# EnvSens.net
KiCad netlist of a schematic drawn in EAGLE
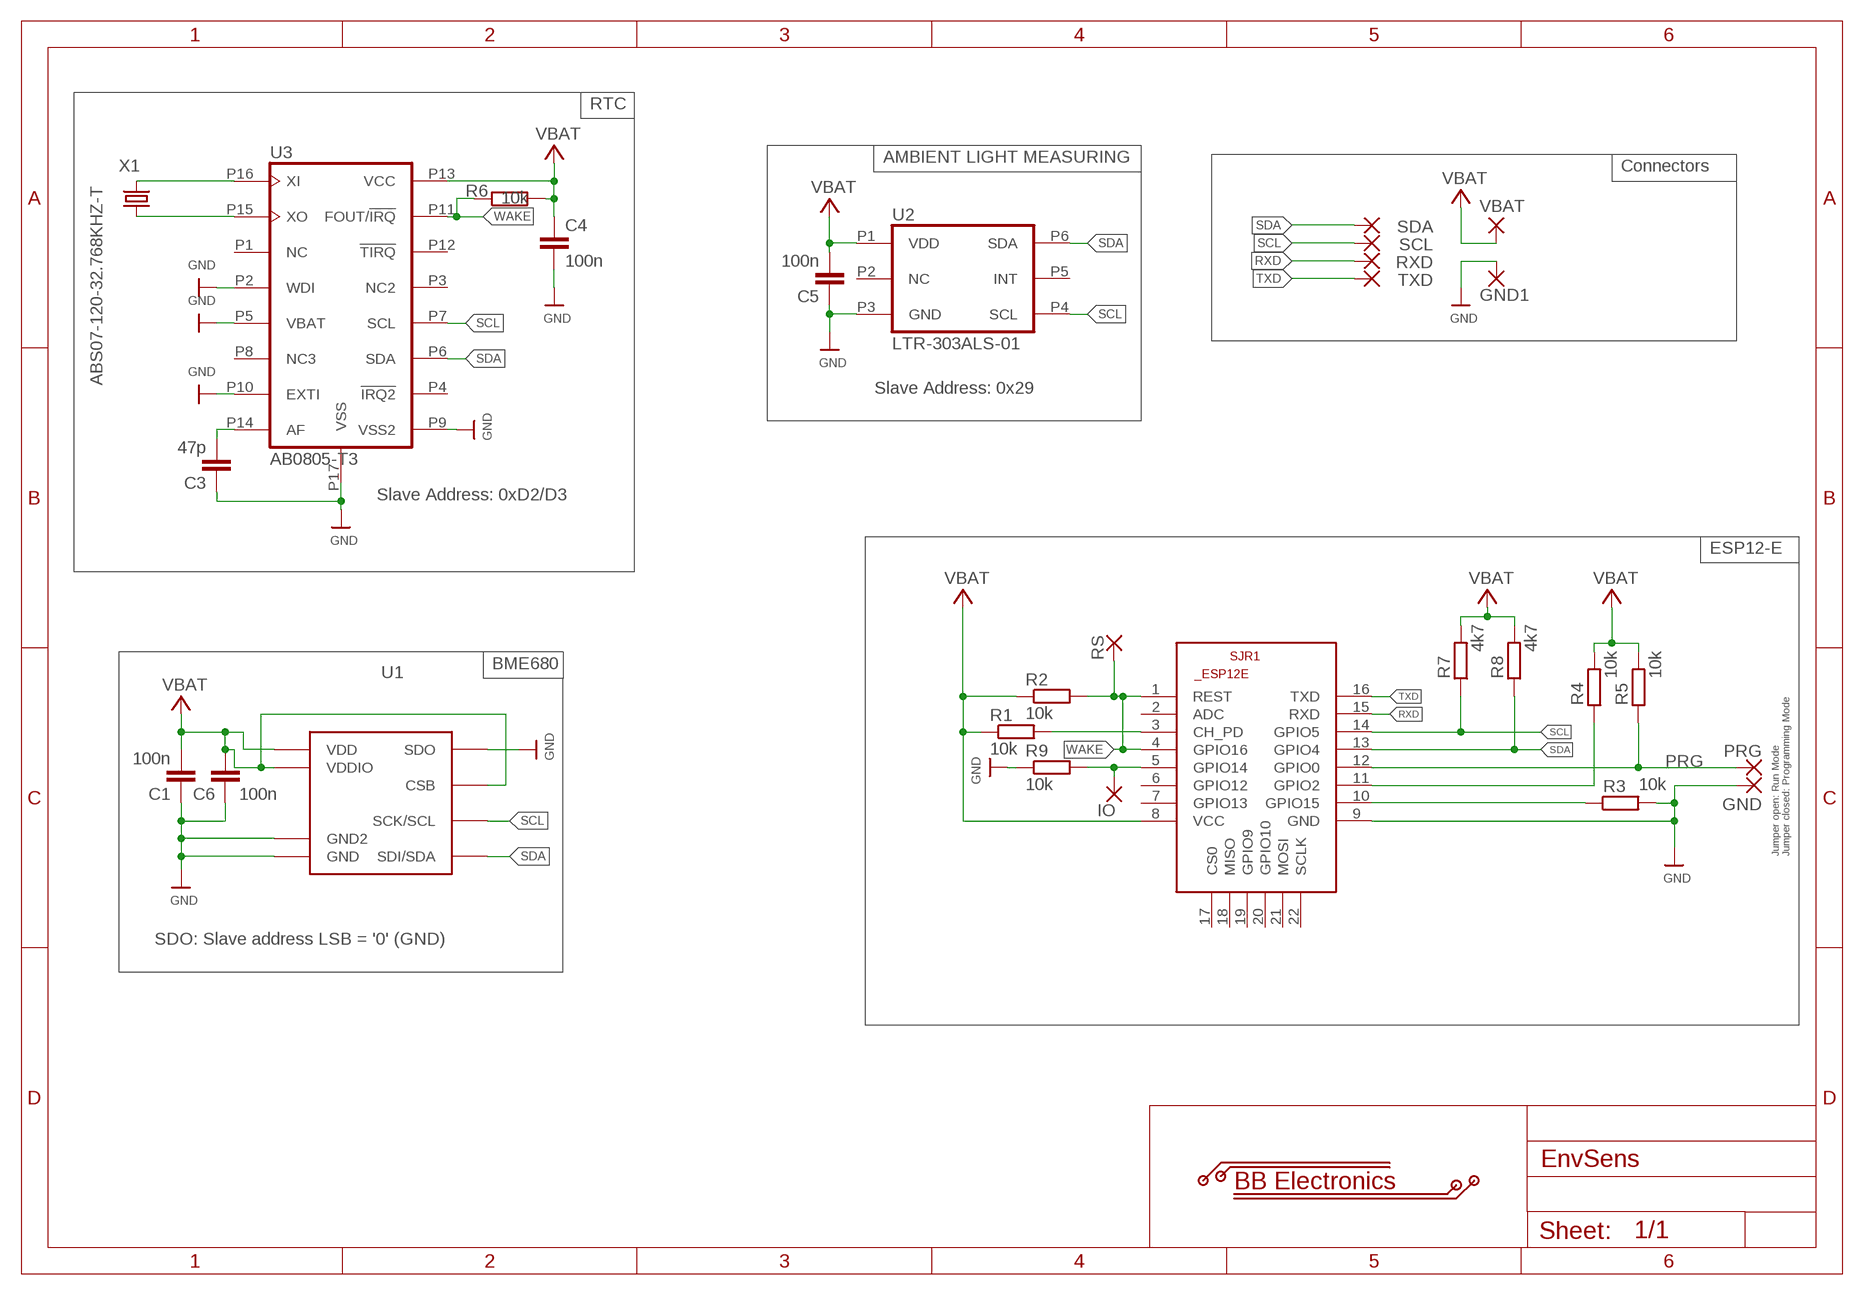
[diagram p0: schematic, sheet 1]

(export (version "E")
  (design (tool "Eeschema 10.0.6"))
  (components
    (comp (ref "C1")
      (value "100n")
      (footprint "eagle-import:0603")
      (libsource (lib "eagle-import") (part "C0603"))
    )
    (comp (ref "C3")
      (value "47p")
      (footprint "eagle-import:0603")
      (libsource (lib "eagle-import") (part "C0603"))
    )
    (comp (ref "C4")
      (value "100n")
      (footprint "eagle-import:0603")
      (libsource (lib "eagle-import") (part "C0603"))
    )
    (comp (ref "C5")
      (value "100n")
      (footprint "eagle-import:0603")
      (libsource (lib "eagle-import") (part "C0603"))
    )
    (comp (ref "C6")
      (value "100n")
      (footprint "eagle-import:0603")
      (libsource (lib "eagle-import") (part "C0603"))
    )
    (comp (ref "GND")
      (value "SMD2")
      (footprint "eagle-import:SMD1,27-2,54")
      (libsource (lib "eagle-import") (part "SMD2"))
    )
    (comp (ref "GND1")
      (value "SMD5")
      (footprint "eagle-import:SMD2,54-5,08")
      (libsource (lib "eagle-import") (part "SMD5"))
    )
    (comp (ref "IO")
      (value "SMD2")
      (footprint "eagle-import:SMD1,27-2,54")
      (libsource (lib "eagle-import") (part "SMD2"))
    )
    (comp (ref "PRG")
      (value "SMD2")
      (footprint "eagle-import:SMD1,27-2,54")
      (libsource (lib "eagle-import") (part "SMD2"))
    )
    (comp (ref "R1")
      (value "10k")
      (footprint "eagle-import:0603")
      (libsource (lib "eagle-import") (part "R0603"))
    )
    (comp (ref "R2")
      (value "10k")
      (footprint "eagle-import:0603")
      (libsource (lib "eagle-import") (part "R0603"))
    )
    (comp (ref "R3")
      (value "10k")
      (footprint "eagle-import:0603")
      (libsource (lib "eagle-import") (part "R0603"))
    )
    (comp (ref "R4")
      (value "10k")
      (footprint "eagle-import:0603")
      (libsource (lib "eagle-import") (part "R0603"))
    )
    (comp (ref "R5")
      (value "10k")
      (footprint "eagle-import:0603")
      (libsource (lib "eagle-import") (part "R0603"))
    )
    (comp (ref "R6")
      (value "10k")
      (footprint "eagle-import:0603")
      (libsource (lib "eagle-import") (part "R0603"))
    )
    (comp (ref "R7")
      (value "4k7")
      (footprint "eagle-import:0603")
      (libsource (lib "eagle-import") (part "R0603"))
    )
    (comp (ref "R8")
      (value "4k7")
      (footprint "eagle-import:0603")
      (libsource (lib "eagle-import") (part "R0603"))
    )
    (comp (ref "R9")
      (value "10k")
      (footprint "eagle-import:0603")
      (libsource (lib "eagle-import") (part "R0603"))
    )
    (comp (ref "RS")
      (value "SMD2")
      (footprint "eagle-import:SMD1,27-2,54")
      (libsource (lib "eagle-import") (part "SMD2"))
    )
    (comp (ref "RXD")
      (value "SMD2")
      (footprint "eagle-import:SMD1,27-2,54")
      (libsource (lib "eagle-import") (part "SMD2"))
    )
    (comp (ref "SCL")
      (value "SMD2")
      (footprint "eagle-import:SMD1,27-2,54")
      (libsource (lib "eagle-import") (part "SMD2"))
    )
    (comp (ref "SDA")
      (value "SMD2")
      (footprint "eagle-import:SMD1,27-2,54")
      (libsource (lib "eagle-import") (part "SMD2"))
    )
    (comp (ref "SJR1")
      (value "ESP8266-12EESP12E")
      (footprint "eagle-import:ESP8266-ESP12E")
      (libsource (lib "eagle-import") (part "ESP8266-12EESP12E"))
    )
    (comp (ref "TXD")
      (value "SMD2")
      (footprint "eagle-import:SMD1,27-2,54")
      (libsource (lib "eagle-import") (part "SMD2"))
    )
    (comp (ref "U1")
      (value "BME680")
      (footprint "eagle-import:BME680")
      (libsource (lib "eagle-import") (part "BME680"))
    )
    (comp (ref "U2")
      (value "LTR-303ALS-01")
      (footprint "eagle-import:6-DFN")
      (libsource (lib "eagle-import") (part "LTR-303ALS-01"))
    )
    (comp (ref "U3")
      (value "AB0805-T3")
      (footprint "eagle-import:16-VFQFN")
      (libsource (lib "eagle-import") (part "AB0805-T3"))
    )
    (comp (ref "VBAT")
      (value "SMD5")
      (footprint "eagle-import:SMD2,54-5,08")
      (libsource (lib "eagle-import") (part "SMD5"))
    )
    (comp (ref "X1")
      (value "ABS07-120-32.768KHZ-T")
      (footprint "eagle-import:ABS07-120-32.768KHZ-T")
      (libsource (lib "eagle-import") (part "ABS07-120-32.768KHZ-T"))
    )
  )
  (nets
    (net (code "1") (name "/PRG") (class "Default")
      (node (ref "PRG") (pin "1") (pinfunction "P_1") (pintype "passive"))
      (node (ref "R5") (pin "P1") (pinfunction "1_P1") (pintype "passive"))
      (node (ref "SJR1") (pin "12") (pinfunction "GPIO0_12") (pintype "bidirectional"))
    )
    (net (code "2") (name "GND") (class "Default")
      (node (ref "C1") (pin "P1") (pinfunction "1_P1") (pintype "passive"))
      (node (ref "C3") (pin "P1") (pinfunction "1_P1") (pintype "passive"))
      (node (ref "C4") (pin "P2") (pinfunction "2_P2") (pintype "passive"))
      (node (ref "C5") (pin "P1") (pinfunction "1_P1") (pintype "passive"))
      (node (ref "C6") (pin "P1") (pinfunction "1_P1") (pintype "passive"))
      (node (ref "GND") (pin "1") (pinfunction "P_1") (pintype "passive"))
      (node (ref "GND1") (pin "1") (pinfunction "P_1") (pintype "passive"))
      (node (ref "R3") (pin "P2") (pinfunction "2_P2") (pintype "passive"))
      (node (ref "R9") (pin "P1") (pinfunction "1_P1") (pintype "passive"))
      (node (ref "SJR1") (pin "9") (pinfunction "GND_9") (pintype "bidirectional"))
      (node (ref "U1") (pin "P1") (pinfunction "GND_P1") (pintype "power_in"))
      (node (ref "U1") (pin "P5") (pinfunction "SDO_P5") (pintype "bidirectional"))
      (node (ref "U1") (pin "P7") (pinfunction "GND2_P7") (pintype "power_in"))
      (node (ref "U2") (pin "P3") (pinfunction "GND_P3") (pintype "power_in"))
      (node (ref "U3") (pin "P10") (pinfunction "EXTI_P10") (pintype "input"))
      (node (ref "U3") (pin "P17") (pinfunction "VSS_P17") (pintype "power_in"))
      (node (ref "U3") (pin "P2") (pinfunction "WDI_P2") (pintype "input"))
      (node (ref "U3") (pin "P5") (pinfunction "VBAT_P5") (pintype "power_in"))
      (node (ref "U3") (pin "P9") (pinfunction "VSS2_P9") (pintype "power_in"))
    )
    (net (code "3") (name "Net-(C3-2)") (class "Default")
      (node (ref "C3") (pin "P2") (pinfunction "2_P2") (pintype "passive"))
      (node (ref "U3") (pin "P14") (pinfunction "AF_P14") (pintype "output"))
    )
    (net (code "4") (name "Net-(IO-P)") (class "Default")
      (node (ref "IO") (pin "1") (pinfunction "P_1") (pintype "passive"))
      (node (ref "R9") (pin "P2") (pinfunction "2_P2") (pintype "passive"))
      (node (ref "SJR1") (pin "5") (pinfunction "GPIO14_5") (pintype "bidirectional"))
    )
    (net (code "5") (name "Net-(R1-2)") (class "Default")
      (node (ref "R1") (pin "P2") (pinfunction "2_P2") (pintype "passive"))
      (node (ref "SJR1") (pin "3") (pinfunction "CH_PD_3") (pintype "bidirectional"))
    )
    (net (code "6") (name "Net-(R3-1)") (class "Default")
      (node (ref "R3") (pin "P1") (pinfunction "1_P1") (pintype "passive"))
      (node (ref "SJR1") (pin "10") (pinfunction "GPIO15_10") (pintype "bidirectional"))
    )
    (net (code "7") (name "Net-(R4-1)") (class "Default")
      (node (ref "R4") (pin "P1") (pinfunction "1_P1") (pintype "passive"))
      (node (ref "SJR1") (pin "11") (pinfunction "GPIO2_11") (pintype "bidirectional"))
    )
    (net (code "8") (name "Net-(U3-XI)") (class "Default")
      (node (ref "U3") (pin "P16") (pinfunction "XI_P16") (pintype "bidirectional"))
      (node (ref "X1") (pin "P2") (pinfunction "2_P2") (pintype "passive"))
    )
    (net (code "9") (name "Net-(U3-XO)") (class "Default")
      (node (ref "U3") (pin "P15") (pinfunction "XO_P15") (pintype "bidirectional"))
      (node (ref "X1") (pin "P1") (pinfunction "1_P1") (pintype "passive"))
    )
    (net (code "10") (name "RXD") (class "Default")
      (node (ref "RXD") (pin "1") (pinfunction "P_1") (pintype "passive"))
      (node (ref "SJR1") (pin "15") (pinfunction "RXD_15") (pintype "bidirectional"))
    )
    (net (code "11") (name "SCL") (class "Default")
      (node (ref "R7") (pin "P1") (pinfunction "1_P1") (pintype "passive"))
      (node (ref "SCL") (pin "1") (pinfunction "P_1") (pintype "passive"))
      (node (ref "SJR1") (pin "14") (pinfunction "GPIO5_14") (pintype "bidirectional"))
      (node (ref "U1") (pin "P4") (pinfunction "SCK/SCL_P4") (pintype "bidirectional"))
      (node (ref "U2") (pin "P4") (pinfunction "SCL_P4") (pintype "bidirectional"))
      (node (ref "U3") (pin "P7") (pinfunction "SCL_P7") (pintype "input"))
    )
    (net (code "12") (name "SDA") (class "Default")
      (node (ref "R8") (pin "P1") (pinfunction "1_P1") (pintype "passive"))
      (node (ref "SDA") (pin "1") (pinfunction "P_1") (pintype "passive"))
      (node (ref "SJR1") (pin "13") (pinfunction "GPIO4_13") (pintype "bidirectional"))
      (node (ref "U1") (pin "P3") (pinfunction "SDI/SDA_P3") (pintype "bidirectional"))
      (node (ref "U2") (pin "P6") (pinfunction "SDA_P6") (pintype "bidirectional"))
      (node (ref "U3") (pin "P6") (pinfunction "SDA_P6") (pintype "bidirectional"))
    )
    (net (code "13") (name "TXD") (class "Default")
      (node (ref "SJR1") (pin "16") (pinfunction "TXD_16") (pintype "bidirectional"))
      (node (ref "TXD") (pin "1") (pinfunction "P_1") (pintype "passive"))
    )
    (net (code "14") (name "VBAT") (class "Default")
      (node (ref "C1") (pin "P2") (pinfunction "2_P2") (pintype "passive"))
      (node (ref "C4") (pin "P1") (pinfunction "1_P1") (pintype "passive"))
      (node (ref "C5") (pin "P2") (pinfunction "2_P2") (pintype "passive"))
      (node (ref "C6") (pin "P2") (pinfunction "2_P2") (pintype "passive"))
      (node (ref "R1") (pin "P1") (pinfunction "1_P1") (pintype "passive"))
      (node (ref "R2") (pin "P1") (pinfunction "1_P1") (pintype "passive"))
      (node (ref "R4") (pin "P2") (pinfunction "2_P2") (pintype "passive"))
      (node (ref "R5") (pin "P2") (pinfunction "2_P2") (pintype "passive"))
      (node (ref "R6") (pin "P2") (pinfunction "2_P2") (pintype "passive"))
      (node (ref "R7") (pin "P2") (pinfunction "2_P2") (pintype "passive"))
      (node (ref "R8") (pin "P2") (pinfunction "2_P2") (pintype "passive"))
      (node (ref "SJR1") (pin "8") (pinfunction "VCC_8") (pintype "bidirectional"))
      (node (ref "U1") (pin "P2") (pinfunction "CSB_P2") (pintype "bidirectional"))
      (node (ref "U1") (pin "P6") (pinfunction "VDDIO_P6") (pintype "power_in"))
      (node (ref "U1") (pin "P8") (pinfunction "VDD_P8") (pintype "power_in"))
      (node (ref "U2") (pin "P1") (pinfunction "VDD_P1") (pintype "power_in"))
      (node (ref "U3") (pin "P13") (pinfunction "VCC_P13") (pintype "power_in"))
      (node (ref "VBAT") (pin "1") (pinfunction "P_1") (pintype "passive"))
    )
    (net (code "15") (name "WAKE") (class "Default")
      (node (ref "R2") (pin "P2") (pinfunction "2_P2") (pintype "passive"))
      (node (ref "R6") (pin "P1") (pinfunction "1_P1") (pintype "passive"))
      (node (ref "RS") (pin "1") (pinfunction "P_1") (pintype "passive"))
      (node (ref "SJR1") (pin "1") (pinfunction "REST_1") (pintype "bidirectional"))
      (node (ref "SJR1") (pin "4") (pinfunction "GPIO16_4") (pintype "bidirectional"))
      (node (ref "U3") (pin "P11") (pinfunction "FOUT/~{IRQ}_P11") (pintype "output"))
    )
    (net (code "16") (name "unconnected-(SJR1-ADC-Pad2)") (class "Default")
      (node (ref "SJR1") (pin "2") (pinfunction "ADC_2") (pintype "bidirectional"))
    )
    (net (code "17") (name "unconnected-(SJR1-CS0-Pad17)") (class "Default")
      (node (ref "SJR1") (pin "17") (pinfunction "CS0_17") (pintype "bidirectional"))
    )
    (net (code "18") (name "unconnected-(SJR1-GPIO9-Pad19)") (class "Default")
      (node (ref "SJR1") (pin "19") (pinfunction "GPIO9_19") (pintype "bidirectional"))
    )
    (net (code "19") (name "unconnected-(SJR1-GPIO10-Pad20)") (class "Default")
      (node (ref "SJR1") (pin "20") (pinfunction "GPIO10_20") (pintype "bidirectional"))
    )
    (net (code "20") (name "unconnected-(SJR1-GPIO12-Pad6)") (class "Default")
      (node (ref "SJR1") (pin "6") (pinfunction "GPIO12_6") (pintype "bidirectional"))
    )
    (net (code "21") (name "unconnected-(SJR1-GPIO13-Pad7)") (class "Default")
      (node (ref "SJR1") (pin "7") (pinfunction "GPIO13_7") (pintype "bidirectional"))
    )
    (net (code "22") (name "unconnected-(SJR1-MISO-Pad18)") (class "Default")
      (node (ref "SJR1") (pin "18") (pinfunction "MISO_18") (pintype "bidirectional"))
    )
    (net (code "23") (name "unconnected-(SJR1-MOSI-Pad21)") (class "Default")
      (node (ref "SJR1") (pin "21") (pinfunction "MOSI_21") (pintype "bidirectional"))
    )
    (net (code "24") (name "unconnected-(SJR1-SCLK-Pad22)") (class "Default")
      (node (ref "SJR1") (pin "22") (pinfunction "SCLK_22") (pintype "bidirectional"))
    )
    (net (code "25") (name "unconnected-(U2-INT-PadP5)") (class "Default")
      (node (ref "U2") (pin "P5") (pinfunction "INT_P5") (pintype "output"))
    )
    (net (code "26") (name "unconnected-(U2-NC-PadP2)") (class "Default")
      (node (ref "U2") (pin "P2") (pinfunction "NC_P2") (pintype "no_connect"))
    )
    (net (code "27") (name "unconnected-(U3-NC-PadP1)") (class "Default")
      (node (ref "U3") (pin "P1") (pinfunction "NC_P1") (pintype "no_connect"))
    )
    (net (code "28") (name "unconnected-(U3-NC2-PadP3)") (class "Default")
      (node (ref "U3") (pin "P3") (pinfunction "NC2_P3") (pintype "no_connect"))
    )
    (net (code "29") (name "unconnected-(U3-NC3-PadP8)") (class "Default")
      (node (ref "U3") (pin "P8") (pinfunction "NC3_P8") (pintype "no_connect"))
    )
    (net (code "30") (name "unconnected-(U3-~{IRQ2}-PadP4)") (class "Default")
      (node (ref "U3") (pin "P4") (pinfunction "~{IRQ2}_P4") (pintype "bidirectional"))
    )
    (net (code "31") (name "unconnected-(U3-~{TIRQ}-PadP12)") (class "Default")
      (node (ref "U3") (pin "P12") (pinfunction "~{TIRQ}_P12") (pintype "input"))
    )
  )
)
